# CH3.net
KiCad netlist of a schematic drawn in Altium Designer
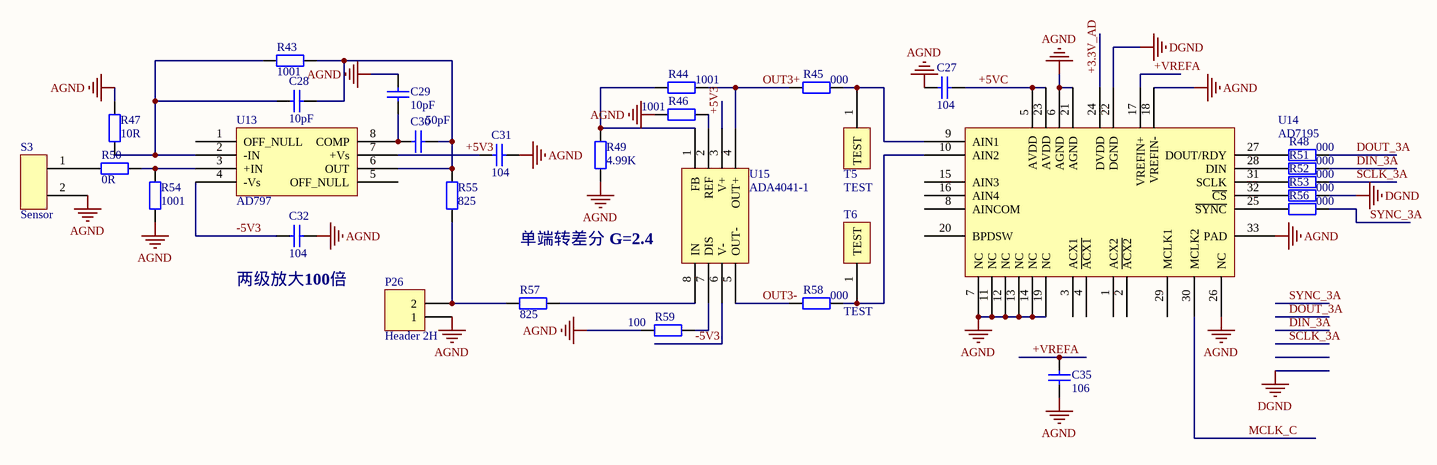
[diagram p0: CH3.SchDoc]

(export (version "E")
  (design (tool "Eeschema 10.0.6"))
  (components
    (comp (ref "C27")
      (value "104")
      (footprint "0603")
      (description "Capacitor")
      (fields (field (name "PUBLISHER") "Altium Limited"))
      (libsource (lib "Miscellaneous Devices") (part "Cap"))
    )
    (comp (ref "C28")
      (value "10pF")
      (footprint "0603")
      (description "Capacitor")
      (fields (field (name "PUBLISHER") "Altium Limited"))
      (libsource (lib "Miscellaneous Devices") (part "Cap"))
    )
    (comp (ref "C29")
      (value "10pF")
      (footprint "0603")
      (description "Capacitor")
      (fields (field (name "PUBLISHER") "Altium Limited"))
      (libsource (lib "Miscellaneous Devices") (part "Cap"))
    )
    (comp (ref "C30")
      (value "50pF")
      (footprint "0603")
      (description "Capacitor")
      (fields (field (name "PUBLISHER") "Altium Limited"))
      (libsource (lib "Miscellaneous Devices") (part "Cap"))
    )
    (comp (ref "C31")
      (value "104")
      (footprint "0603")
      (description "Capacitor")
      (fields (field (name "PUBLISHER") "Altium Limited"))
      (libsource (lib "Miscellaneous Devices") (part "Cap"))
    )
    (comp (ref "C32")
      (value "104")
      (footprint "0603")
      (description "Capacitor")
      (fields (field (name "PUBLISHER") "Altium Limited"))
      (libsource (lib "Miscellaneous Devices") (part "Cap"))
    )
    (comp (ref "C35")
      (value "106")
      (footprint "0603")
      (description "Capacitor")
      (fields (field (name "PUBLISHER") "Altium Limited"))
      (libsource (lib "Miscellaneous Devices") (part "Cap"))
    )
    (comp (ref "P26")
      (value "Header 2H")
      (footprint "HDR1X2")
      (description "Header, 2-Pin, Right Angle")
      (fields (field (name "PUBLISHER") "Altium Limited"))
      (libsource (lib "Miscellaneous Connectors") (part "Header 2H"))
    )
    (comp (ref "R43")
      (value "1001")
      (footprint "0603")
      (description "Resistor")
      (fields (field (name "PUBLISHER") "Altium Limited"))
      (libsource (lib "Miscellaneous Devices") (part "Res2"))
    )
    (comp (ref "R44")
      (value "1001")
      (footprint "0603")
      (description "Resistor")
      (fields (field (name "PUBLISHER") "Altium Limited"))
      (libsource (lib "Miscellaneous Devices") (part "Res2"))
    )
    (comp (ref "R45")
      (value "000")
      (footprint "0603")
      (description "Resistor")
      (fields (field (name "PUBLISHER") "Altium Limited"))
      (libsource (lib "Miscellaneous Devices") (part "Res2"))
    )
    (comp (ref "R46")
      (value "1001")
      (footprint "0603")
      (description "Resistor")
      (fields (field (name "PUBLISHER") "Altium Limited"))
      (libsource (lib "Miscellaneous Devices") (part "Res2"))
    )
    (comp (ref "R47")
      (value "10R")
      (footprint "0603")
      (description "Resistor")
      (fields (field (name "PUBLISHER") "Altium Limited"))
      (libsource (lib "") (part "Res2_2"))
    )
    (comp (ref "R48")
      (value "000")
      (footprint "0603")
      (description "Resistor")
      (fields (field (name "PUBLISHER") "Altium Limited"))
      (libsource (lib "Miscellaneous Devices") (part "Res2"))
    )
    (comp (ref "R49")
      (value "4.99K")
      (footprint "0603")
      (description "Resistor")
      (fields (field (name "PUBLISHER") "Altium Limited"))
      (libsource (lib "") (part "Res2_1"))
    )
    (comp (ref "R50")
      (value "0R")
      (footprint "0603")
      (description "Resistor")
      (fields (field (name "PUBLISHER") "Altium Limited"))
      (libsource (lib "Miscellaneous Devices") (part "Res2"))
    )
    (comp (ref "R51")
      (value "000")
      (footprint "0603")
      (description "Resistor")
      (fields (field (name "PUBLISHER") "Altium Limited"))
      (libsource (lib "Miscellaneous Devices") (part "Res2"))
    )
    (comp (ref "R52")
      (value "000")
      (footprint "0603")
      (description "Resistor")
      (fields (field (name "PUBLISHER") "Altium Limited"))
      (libsource (lib "Miscellaneous Devices") (part "Res2"))
    )
    (comp (ref "R53")
      (value "000")
      (footprint "0603")
      (description "Resistor")
      (fields (field (name "PUBLISHER") "Altium Limited"))
      (libsource (lib "Miscellaneous Devices") (part "Res2"))
    )
    (comp (ref "R54")
      (value "1001")
      (footprint "0603")
      (description "Resistor")
      (fields (field (name "PUBLISHER") "Altium Limited"))
      (libsource (lib "") (part "Res2_1"))
    )
    (comp (ref "R55")
      (value "825")
      (footprint "0603")
      (description "Resistor")
      (fields (field (name "PUBLISHER") "Altium Limited"))
      (libsource (lib "") (part "Res2_1"))
    )
    (comp (ref "R56")
      (value "000")
      (footprint "0603")
      (description "Resistor")
      (fields (field (name "PUBLISHER") "Altium Limited"))
      (libsource (lib "Miscellaneous Devices") (part "Res2"))
    )
    (comp (ref "R57")
      (value "825")
      (footprint "0603")
      (description "Resistor")
      (fields (field (name "PUBLISHER") "Altium Limited"))
      (libsource (lib "Miscellaneous Devices") (part "Res2"))
    )
    (comp (ref "R58")
      (value "000")
      (footprint "0603")
      (description "Resistor")
      (fields (field (name "PUBLISHER") "Altium Limited"))
      (libsource (lib "Miscellaneous Devices") (part "Res2"))
    )
    (comp (ref "R59")
      (value "100")
      (footprint "0603")
      (description "Resistor")
      (fields (field (name "PUBLISHER") "Altium Limited"))
      (libsource (lib "Miscellaneous Devices") (part "Res2"))
    )
    (comp (ref "S3") (value "Sensor") (footprint "HDR1X2") (libsource (lib "Schlib1") (part "Sensor")))
    (comp (ref "T5") (value "TEST") (footprint "TEST") (libsource (lib "") (part "TEST_1")))
    (comp (ref "T6") (value "TEST") (footprint "TEST") (libsource (lib "Schlib1") (part "TEST")))
    (comp (ref "U13") (value "AD797") (footprint "SO8") (libsource (lib "Schlib1") (part "AD797")))
    (comp (ref "U14") (value "AD7195") (footprint "VQFN32") (libsource (lib "Schlib1") (part "AD7195")))
    (comp (ref "U15") (value "ADA4041-1") (footprint "SO8") (libsource (lib "Schlib1") (part "ADA4041-1")))
  )
  (nets
    (net (code "1") (name "/+3.3V_AD") (class "Default")
      (node (ref "U14") (pin "24") (pinfunction "DVDD_24") (pintype "passive"))
    )
    (net (code "2") (name "/+5V3") (class "Default")
      (node (ref "C31") (pin "2") (pinfunction "2_2") (pintype "passive"))
      (node (ref "U13") (pin "7") (pinfunction "+Vs_7") (pintype "passive"))
      (node (ref "U15") (pin "3") (pinfunction "V+_3") (pintype "passive"))
    )
    (net (code "3") (name "/+5VC") (class "Default")
      (node (ref "C27") (pin "2") (pinfunction "2_2") (pintype "passive"))
      (node (ref "U14") (pin "23") (pinfunction "AVDD_23") (pintype "passive"))
      (node (ref "U14") (pin "5") (pinfunction "AVDD_5") (pintype "passive"))
    )
    (net (code "4") (name "/+VREFA") (class "Default")
      (node (ref "C35") (pin "1") (pinfunction "1_1") (pintype "passive"))
      (node (ref "U14") (pin "17") (pinfunction "VREFIN+_17") (pintype "passive"))
    )
    (net (code "5") (name "/-5V3") (class "Default")
      (node (ref "C32") (pin "2") (pinfunction "2_2") (pintype "passive"))
      (node (ref "U13") (pin "4") (pinfunction "-Vs_4") (pintype "passive"))
      (node (ref "U15") (pin "6") (pinfunction "V-_6") (pintype "passive"))
    )
    (net (code "6") (name "/DIN_3A") (class "Default")
      (node (ref "R51") (pin "2") (pinfunction "2_2") (pintype "passive"))
    )
    (net (code "7") (name "/DOUT_3A") (class "Default")
      (node (ref "R48") (pin "2") (pinfunction "2_2") (pintype "passive"))
    )
    (net (code "8") (name "/MCLK_C") (class "Default")
      (node (ref "U14") (pin "30") (pinfunction "MCLK2_30") (pintype "passive"))
    )
    (net (code "9") (name "/OUT3+") (class "Default")
      (node (ref "R44") (pin "2") (pinfunction "2_2") (pintype "passive"))
      (node (ref "R45") (pin "1") (pinfunction "1_1") (pintype "passive"))
      (node (ref "U15") (pin "4") (pinfunction "OUT+_4") (pintype "passive"))
    )
    (net (code "10") (name "/OUT3-") (class "Default")
      (node (ref "R58") (pin "1") (pinfunction "1_1") (pintype "passive"))
      (node (ref "U15") (pin "5") (pinfunction "OUT-_5") (pintype "passive"))
    )
    (net (code "11") (name "/SCLK_3A") (class "Default")
      (node (ref "R52") (pin "2") (pinfunction "2_2") (pintype "passive"))
    )
    (net (code "12") (name "/SYNC_3A") (class "Default")
      (node (ref "R56") (pin "2") (pinfunction "2_2") (pintype "passive"))
    )
    (net (code "13") (name "AGND") (class "Default")
      (node (ref "C27") (pin "1") (pinfunction "1_1") (pintype "passive"))
      (node (ref "C29") (pin "2") (pinfunction "2_2") (pintype "passive"))
      (node (ref "C31") (pin "1") (pinfunction "1_1") (pintype "passive"))
      (node (ref "C32") (pin "1") (pinfunction "1_1") (pintype "passive"))
      (node (ref "C35") (pin "2") (pinfunction "2_2") (pintype "passive"))
      (node (ref "P26") (pin "1") (pinfunction "1_1") (pintype "passive"))
      (node (ref "R46") (pin "1") (pinfunction "1_1") (pintype "passive"))
      (node (ref "R47") (pin "1") (pinfunction "1_1") (pintype "passive"))
      (node (ref "R49") (pin "1") (pinfunction "1_1") (pintype "passive"))
      (node (ref "R54") (pin "1") (pinfunction "1_1") (pintype "passive"))
      (node (ref "R59") (pin "1") (pinfunction "1_1") (pintype "passive"))
      (node (ref "S3") (pin "2") (pinfunction "2_2") (pintype "passive"))
      (node (ref "U14") (pin "11") (pinfunction "NC_11") (pintype "passive"))
      (node (ref "U14") (pin "12") (pinfunction "NC_12") (pintype "passive"))
      (node (ref "U14") (pin "13") (pinfunction "NC_13") (pintype "passive"))
      (node (ref "U14") (pin "14") (pinfunction "NC_14") (pintype "passive"))
      (node (ref "U14") (pin "18") (pinfunction "VREFIN-_18") (pintype "passive"))
      (node (ref "U14") (pin "19") (pinfunction "NC_19") (pintype "passive"))
      (node (ref "U14") (pin "21") (pinfunction "AGND_21") (pintype "passive"))
      (node (ref "U14") (pin "26") (pinfunction "NC_26") (pintype "passive"))
      (node (ref "U14") (pin "33") (pinfunction "PAD_33") (pintype "passive"))
      (node (ref "U14") (pin "6") (pinfunction "AGND_6") (pintype "passive"))
      (node (ref "U14") (pin "7") (pinfunction "NC_7") (pintype "passive"))
    )
    (net (code "14") (name "DGND") (class "Default")
      (node (ref "R53") (pin "2") (pinfunction "2_2") (pintype "passive"))
      (node (ref "U14") (pin "22") (pinfunction "DGND_22") (pintype "passive"))
    )
    (net (code "15") (name "Net-(P26-Pad2)") (class "Default")
      (node (ref "P26") (pin "2") (pinfunction "2_2") (pintype "passive"))
      (node (ref "R55") (pin "1") (pinfunction "1_1") (pintype "passive"))
      (node (ref "R57") (pin "1") (pinfunction "1_1") (pintype "passive"))
    )
    (net (code "16") (name "Net-(R50-Pad1)") (class "Default")
      (node (ref "R50") (pin "1") (pinfunction "1_1") (pintype "passive"))
      (node (ref "S3") (pin "1") (pinfunction "1_1") (pintype "passive"))
    )
    (net (code "17") (name "Net-(T5-TEST)") (class "Default")
      (node (ref "R45") (pin "2") (pinfunction "2_2") (pintype "passive"))
      (node (ref "T5") (pin "1") (pinfunction "TEST_1") (pintype "passive"))
      (node (ref "U14") (pin "9") (pinfunction "AIN1_9") (pintype "passive"))
    )
    (net (code "18") (name "Net-(T6-TEST)") (class "Default")
      (node (ref "R58") (pin "2") (pinfunction "2_2") (pintype "passive"))
      (node (ref "T6") (pin "1") (pinfunction "TEST_1") (pintype "passive"))
      (node (ref "U14") (pin "10") (pinfunction "AIN2_10") (pintype "passive"))
    )
    (net (code "19") (name "Net-(U13-+IN)") (class "Default")
      (node (ref "R50") (pin "2") (pinfunction "2_2") (pintype "passive"))
      (node (ref "R54") (pin "2") (pinfunction "2_2") (pintype "passive"))
      (node (ref "U13") (pin "3") (pinfunction "+IN_3") (pintype "passive"))
    )
    (net (code "20") (name "Net-(U13--IN)") (class "Default")
      (node (ref "C28") (pin "2") (pinfunction "2_2") (pintype "passive"))
      (node (ref "R43") (pin "1") (pinfunction "1_1") (pintype "passive"))
      (node (ref "R47") (pin "2") (pinfunction "2_2") (pintype "passive"))
      (node (ref "U13") (pin "2") (pinfunction "-IN_2") (pintype "passive"))
    )
    (net (code "21") (name "Net-(U13-COMP)") (class "Default")
      (node (ref "C29") (pin "1") (pinfunction "1_1") (pintype "passive"))
      (node (ref "C30") (pin "2") (pinfunction "2_2") (pintype "passive"))
      (node (ref "U13") (pin "8") (pinfunction "COMP_8") (pintype "passive"))
    )
    (net (code "22") (name "Net-(U13-OUT)") (class "Default")
      (node (ref "C28") (pin "1") (pinfunction "1_1") (pintype "passive"))
      (node (ref "C30") (pin "1") (pinfunction "1_1") (pintype "passive"))
      (node (ref "R43") (pin "2") (pinfunction "2_2") (pintype "passive"))
      (node (ref "R55") (pin "2") (pinfunction "2_2") (pintype "passive"))
      (node (ref "U13") (pin "6") (pinfunction "OUT_6") (pintype "passive"))
    )
    (net (code "23") (name "Net-(U14-DIN)") (class "Default")
      (node (ref "R51") (pin "1") (pinfunction "1_1") (pintype "passive"))
      (node (ref "U14") (pin "28") (pinfunction "DIN_28") (pintype "passive"))
    )
    (net (code "24") (name "Net-(U14-DOUT{slash}RDY)") (class "Default")
      (node (ref "R48") (pin "1") (pinfunction "1_1") (pintype "passive"))
      (node (ref "U14") (pin "27") (pinfunction "DOUT/RDY_27") (pintype "passive"))
    )
    (net (code "25") (name "Net-(U14-SCLK)") (class "Default")
      (node (ref "R52") (pin "1") (pinfunction "1_1") (pintype "passive"))
      (node (ref "U14") (pin "31") (pinfunction "SCLK_31") (pintype "passive"))
    )
    (net (code "26") (name "Net-(U14-~{CS})") (class "Default")
      (node (ref "R53") (pin "1") (pinfunction "1_1") (pintype "passive"))
      (node (ref "U14") (pin "32") (pinfunction "~{CS}_32") (pintype "passive"))
    )
    (net (code "27") (name "Net-(U14-~{SYNC})") (class "Default")
      (node (ref "R56") (pin "1") (pinfunction "1_1") (pintype "passive"))
      (node (ref "U14") (pin "25") (pinfunction "~{SYNC}_25") (pintype "passive"))
    )
    (net (code "28") (name "Net-(U15-DIS)") (class "Default")
      (node (ref "R59") (pin "2") (pinfunction "2_2") (pintype "passive"))
      (node (ref "U15") (pin "7") (pinfunction "DIS_7") (pintype "passive"))
    )
    (net (code "29") (name "Net-(U15-FB)") (class "Default")
      (node (ref "R44") (pin "1") (pinfunction "1_1") (pintype "passive"))
      (node (ref "R49") (pin "2") (pinfunction "2_2") (pintype "passive"))
      (node (ref "U15") (pin "1") (pinfunction "FB_1") (pintype "passive"))
    )
    (net (code "30") (name "Net-(U15-IN)") (class "Default")
      (node (ref "R57") (pin "2") (pinfunction "2_2") (pintype "passive"))
      (node (ref "U15") (pin "8") (pinfunction "IN_8") (pintype "passive"))
    )
    (net (code "31") (name "Net-(U15-REF)") (class "Default")
      (node (ref "R46") (pin "2") (pinfunction "2_2") (pintype "passive"))
      (node (ref "U15") (pin "2") (pinfunction "REF_2") (pintype "passive"))
    )
    (net (code "32") (name "unconnected-(U13-OFF_NULL-Pad1)") (class "Default")
      (node (ref "U13") (pin "1") (pinfunction "OFF_NULL_1") (pintype "passive"))
    )
    (net (code "33") (name "unconnected-(U13-OFF_NULL-Pad5)") (class "Default")
      (node (ref "U13") (pin "5") (pinfunction "OFF_NULL_5") (pintype "passive"))
    )
    (net (code "34") (name "unconnected-(U14-ACX1-Pad3)") (class "Default")
      (node (ref "U14") (pin "3") (pinfunction "ACX1_3") (pintype "passive"))
    )
    (net (code "35") (name "unconnected-(U14-ACX2-Pad1)") (class "Default")
      (node (ref "U14") (pin "1") (pinfunction "ACX2_1") (pintype "passive"))
    )
    (net (code "36") (name "unconnected-(U14-AIN3-Pad15)") (class "Default")
      (node (ref "U14") (pin "15") (pinfunction "AIN3_15") (pintype "passive"))
    )
    (net (code "37") (name "unconnected-(U14-AIN4-Pad16)") (class "Default")
      (node (ref "U14") (pin "16") (pinfunction "AIN4_16") (pintype "passive"))
    )
    (net (code "38") (name "unconnected-(U14-AINCOM-Pad8)") (class "Default")
      (node (ref "U14") (pin "8") (pinfunction "AINCOM_8") (pintype "passive"))
    )
    (net (code "39") (name "unconnected-(U14-BPDSW-Pad20)") (class "Default")
      (node (ref "U14") (pin "20") (pinfunction "BPDSW_20") (pintype "passive"))
    )
    (net (code "40") (name "unconnected-(U14-MCLK1-Pad29)") (class "Default")
      (node (ref "U14") (pin "29") (pinfunction "MCLK1_29") (pintype "passive"))
    )
    (net (code "41") (name "unconnected-(U14-~{ACX1}-Pad4)") (class "Default")
      (node (ref "U14") (pin "4") (pinfunction "~{ACX1}_4") (pintype "passive"))
    )
    (net (code "42") (name "unconnected-(U14-~{ACX2}-Pad2)") (class "Default")
      (node (ref "U14") (pin "2") (pinfunction "~{ACX2}_2") (pintype "passive"))
    )
  )
)
